# Adafruit_0_54_Alphanumeric_STEMMA_QT.net
KiCad netlist of a schematic drawn in EAGLE
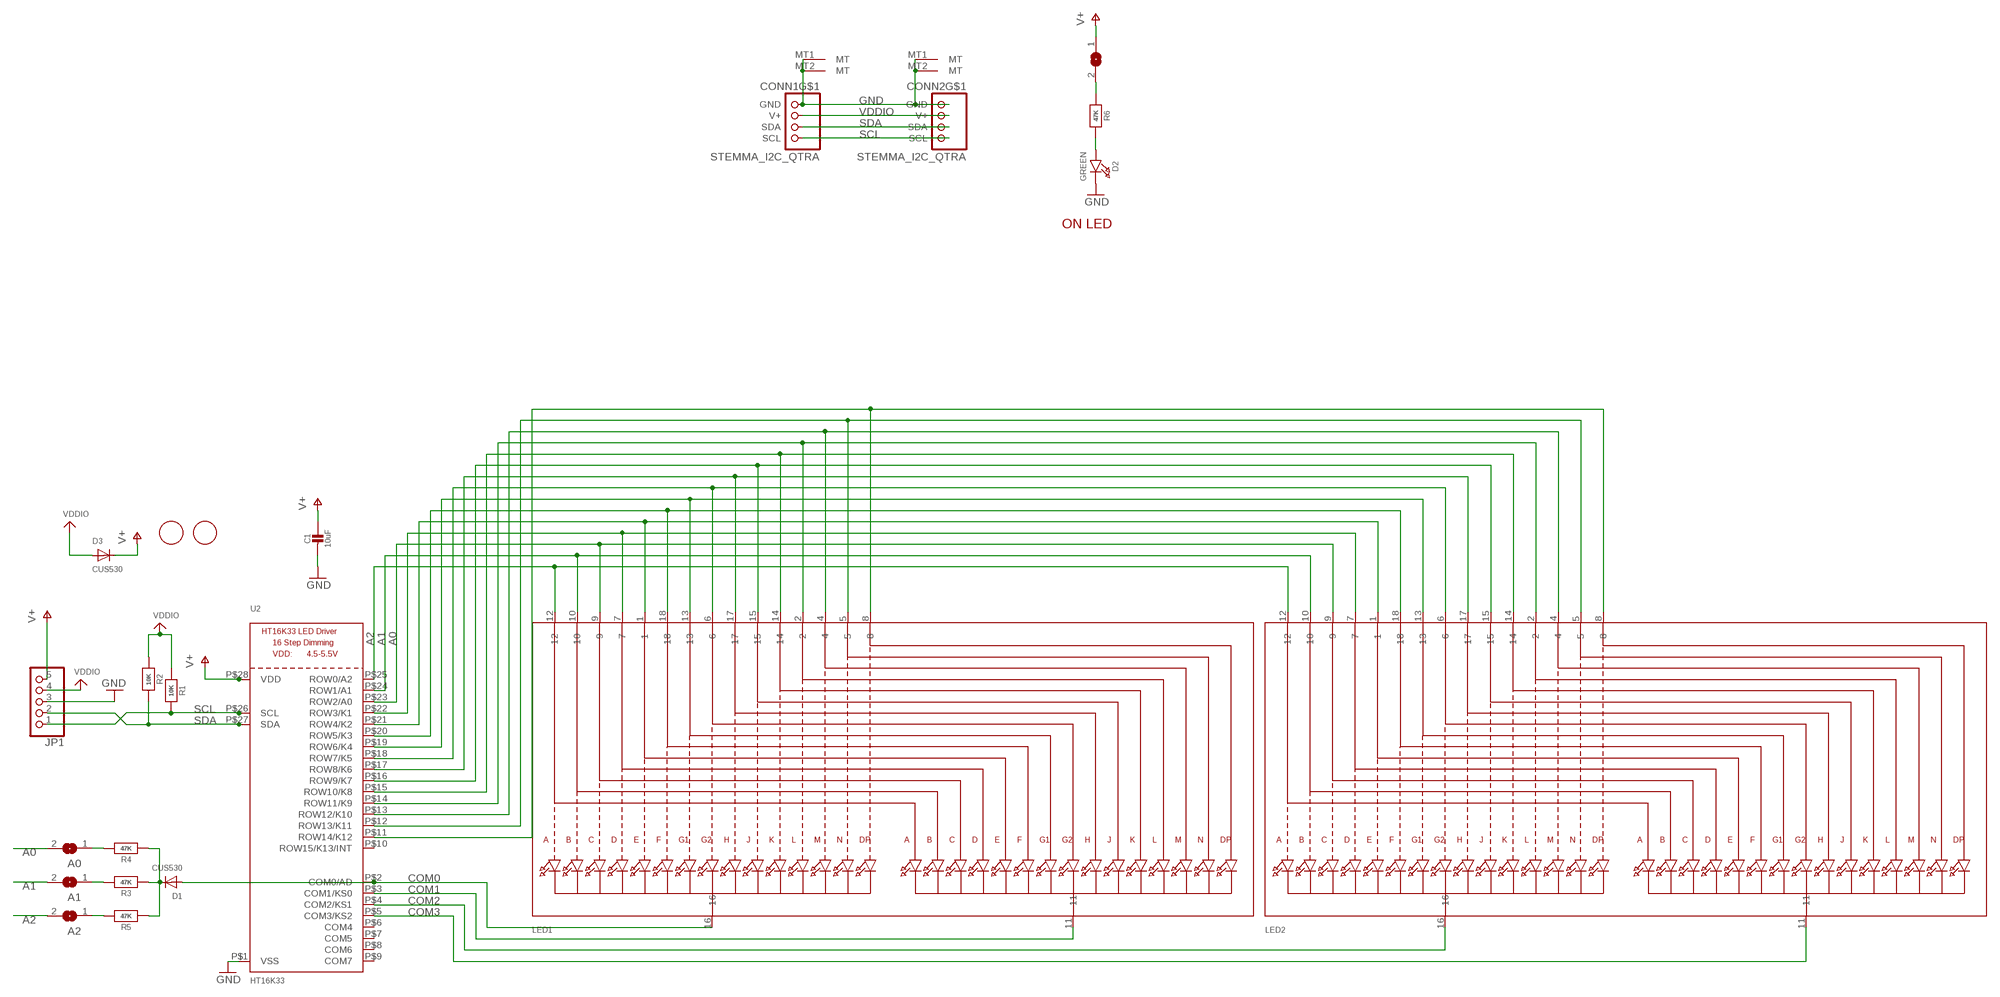
[diagram p0: schematic, sheet 1]

(export (version "E")
  (design (tool "Eeschema 10.0.6"))
  (components
    (comp (ref "A0")
      (value "SOLDERJUMPERREFLOW_NOPASTE")
      (footprint "eagle-import:SOLDERJUMPER_REFLOW_NOPASTE")
      (libsource (lib "eagle-import") (part "SOLDERJUMPERREFLOW_NOPASTE"))
    )
    (comp (ref "A1")
      (value "SOLDERJUMPERREFLOW_NOPASTE")
      (footprint "eagle-import:SOLDERJUMPER_REFLOW_NOPASTE")
      (libsource (lib "eagle-import") (part "SOLDERJUMPERREFLOW_NOPASTE"))
    )
    (comp (ref "A2")
      (value "SOLDERJUMPERREFLOW_NOPASTE")
      (footprint "eagle-import:SOLDERJUMPER_REFLOW_NOPASTE")
      (libsource (lib "eagle-import") (part "SOLDERJUMPERREFLOW_NOPASTE"))
    )
    (comp (ref "C1")
      (value "10uF")
      (footprint "eagle-import:0805-NO")
      (libsource (lib "eagle-import") (part "CAP_CERAMIC0805-NOOUTLINE"))
    )
    (comp (ref "CONN1")
      (value "STEMMA_I2C_QTRA")
      (footprint "eagle-import:JST_SH4_RA")
      (libsource (lib "eagle-import") (part "STEMMA_I2C_QTRA"))
    )
    (comp (ref "CONN2")
      (value "STEMMA_I2C_QTRA")
      (footprint "eagle-import:JST_SH4_RA")
      (libsource (lib "eagle-import") (part "STEMMA_I2C_QTRA"))
    )
    (comp (ref "D1")
      (value "CUS530")
      (footprint "eagle-import:SOD-323F")
      (libsource (lib "eagle-import") (part "DIODESOD-323F"))
    )
    (comp (ref "D2")
      (value "GREEN")
      (footprint "eagle-import:CHIPLED_0603_NOOUTLINE")
      (libsource (lib "eagle-import") (part "LED0603_NOOUTLINE"))
    )
    (comp (ref "D3")
      (value "CUS530")
      (footprint "eagle-import:SOD-323F")
      (libsource (lib "eagle-import") (part "DIODESOD-323F"))
    )
    (comp (ref "JP1")
      (value "HEADER-1X570MIL")
      (footprint "eagle-import:1X05_ROUND_70")
      (libsource (lib "eagle-import") (part "HEADER-1X570MIL"))
    )
    (comp (ref "LED1")
      (value "DISP_SEGMENT_STARBURST_DUAL_COMMONCATHODE")
      (footprint "eagle-import:SEGMENT_STARTBUST_DUAL_KWA-541CBB")
      (libsource (lib "eagle-import") (part "DISP_SEGMENT_STARBURST_DUAL_COMMONCATHODE"))
    )
    (comp (ref "LED2")
      (value "DISP_SEGMENT_STARBURST_DUAL_COMMONCATHODE")
      (footprint "eagle-import:SEGMENT_STARTBUST_DUAL_KWA-541CBB")
      (libsource (lib "eagle-import") (part "DISP_SEGMENT_STARBURST_DUAL_COMMONCATHODE"))
    )
    (comp (ref "LEDJMP")
      (value "SOLDERJUMPERCLOSED")
      (footprint "eagle-import:SOLDERJUMPER_CLOSEDWIRE")
      (libsource (lib "eagle-import") (part "SOLDERJUMPERCLOSED"))
    )
    (comp (ref "R1")
      (value "10K")
      (footprint "eagle-import:0603-NO")
      (libsource (lib "eagle-import") (part "RESISTOR_0603_NOOUT"))
    )
    (comp (ref "R2")
      (value "10K")
      (footprint "eagle-import:0603-NO")
      (libsource (lib "eagle-import") (part "RESISTOR_0603_NOOUT"))
    )
    (comp (ref "R3")
      (value "47K")
      (footprint "eagle-import:0603-NO")
      (libsource (lib "eagle-import") (part "RESISTOR_0603_NOOUT"))
    )
    (comp (ref "R4")
      (value "47K")
      (footprint "eagle-import:0603-NO")
      (libsource (lib "eagle-import") (part "RESISTOR_0603_NOOUT"))
    )
    (comp (ref "R5")
      (value "47K")
      (footprint "eagle-import:0603-NO")
      (libsource (lib "eagle-import") (part "RESISTOR_0603_NOOUT"))
    )
    (comp (ref "R6")
      (value "47K")
      (footprint "eagle-import:0603-NO")
      (libsource (lib "eagle-import") (part "RESISTOR_0603_NOOUT"))
    )
    (comp (ref "U$1")
      (value "FIDUCIAL")
      (footprint "eagle-import:FIDUCIAL_1MM")
      (libsource (lib "eagle-import") (part "FIDUCIAL"))
    )
    (comp (ref "U$2")
      (value "FIDUCIAL")
      (footprint "eagle-import:FIDUCIAL_1MM")
      (libsource (lib "eagle-import") (part "FIDUCIAL"))
    )
    (comp (ref "U2")
      (value "HT16K33")
      (footprint "eagle-import:SOP28_300MIL_SKINNY")
      (libsource (lib "eagle-import") (part "HT16K33_SOP28_SKINNY"))
    )
  )
  (nets
    (net (code "1") (name "/A0") (class "Default")
      (node (ref "A0") (pin "2") (pinfunction "2_2") (pintype "passive"))
      (node (ref "LED1") (pin "9") (pinfunction "9_9") (pintype "bidirectional"))
      (node (ref "LED2") (pin "9") (pinfunction "9_9") (pintype "bidirectional"))
      (node (ref "U2") (pin "P$23") (pinfunction "ROW2/A0_P$23") (pintype "bidirectional"))
    )
    (net (code "2") (name "/A1") (class "Default")
      (node (ref "A1") (pin "2") (pinfunction "2_2") (pintype "passive"))
      (node (ref "LED1") (pin "10") (pinfunction "10_10") (pintype "bidirectional"))
      (node (ref "LED2") (pin "10") (pinfunction "10_10") (pintype "bidirectional"))
      (node (ref "U2") (pin "P$24") (pinfunction "ROW1/A1_P$24") (pintype "bidirectional"))
    )
    (net (code "3") (name "/A2") (class "Default")
      (node (ref "A2") (pin "2") (pinfunction "2_2") (pintype "passive"))
      (node (ref "LED1") (pin "12") (pinfunction "12_12") (pintype "bidirectional"))
      (node (ref "LED2") (pin "12") (pinfunction "12_12") (pintype "bidirectional"))
      (node (ref "U2") (pin "P$25") (pinfunction "ROW0/A2_P$25") (pintype "bidirectional"))
    )
    (net (code "4") (name "/COM0") (class "Default")
      (node (ref "D1") (pin "A") (pinfunction "A_A") (pintype "passive"))
      (node (ref "LED1") (pin "16") (pinfunction "16_16") (pintype "bidirectional"))
      (node (ref "U2") (pin "P$2") (pinfunction "COM0/AD_P$2") (pintype "bidirectional"))
    )
    (net (code "5") (name "/COM1") (class "Default")
      (node (ref "LED1") (pin "11") (pinfunction "11_11") (pintype "bidirectional"))
      (node (ref "U2") (pin "P$3") (pinfunction "COM1/KS0_P$3") (pintype "bidirectional"))
    )
    (net (code "6") (name "/COM2") (class "Default")
      (node (ref "LED2") (pin "16") (pinfunction "16_16") (pintype "bidirectional"))
      (node (ref "U2") (pin "P$4") (pinfunction "COM2/KS1_P$4") (pintype "bidirectional"))
    )
    (net (code "7") (name "/COM3") (class "Default")
      (node (ref "LED2") (pin "11") (pinfunction "11_11") (pintype "bidirectional"))
      (node (ref "U2") (pin "P$5") (pinfunction "COM3/KS2_P$5") (pintype "bidirectional"))
    )
    (net (code "8") (name "/SCL") (class "Default")
      (node (ref "CONN1") (pin "4") (pinfunction "SCL_4") (pintype "passive"))
      (node (ref "CONN2") (pin "4") (pinfunction "SCL_4") (pintype "passive"))
      (node (ref "JP1") (pin "1") (pinfunction "1_1") (pintype "passive"))
      (node (ref "R1") (pin "2") (pinfunction "2_2") (pintype "passive"))
      (node (ref "U2") (pin "P$26") (pinfunction "SCL_P$26") (pintype "bidirectional"))
    )
    (net (code "9") (name "/SDA") (class "Default")
      (node (ref "CONN1") (pin "3") (pinfunction "SDA_3") (pintype "passive"))
      (node (ref "CONN2") (pin "3") (pinfunction "SDA_3") (pintype "passive"))
      (node (ref "JP1") (pin "2") (pinfunction "2_2") (pintype "passive"))
      (node (ref "R2") (pin "2") (pinfunction "2_2") (pintype "passive"))
      (node (ref "U2") (pin "P$27") (pinfunction "SDA_P$27") (pintype "bidirectional"))
    )
    (net (code "10") (name "GND") (class "Default")
      (node (ref "C1") (pin "2") (pinfunction "2_2") (pintype "passive"))
      (node (ref "CONN1") (pin "1") (pinfunction "GND_1") (pintype "passive"))
      (node (ref "CONN1") (pin "MT1") (pinfunction "MT_MT1") (pintype "bidirectional"))
      (node (ref "CONN1") (pin "MT2") (pinfunction "MT_MT2") (pintype "bidirectional"))
      (node (ref "CONN2") (pin "1") (pinfunction "GND_1") (pintype "passive"))
      (node (ref "CONN2") (pin "MT1") (pinfunction "MT_MT1") (pintype "bidirectional"))
      (node (ref "CONN2") (pin "MT2") (pinfunction "MT_MT2") (pintype "bidirectional"))
      (node (ref "D2") (pin "C") (pinfunction "C_C") (pintype "passive"))
      (node (ref "JP1") (pin "3") (pinfunction "3_3") (pintype "passive"))
      (node (ref "U2") (pin "P$1") (pinfunction "VSS_P$1") (pintype "bidirectional"))
    )
    (net (code "11") (name "Net-(A0-Pad1)") (class "Default")
      (node (ref "A0") (pin "1") (pinfunction "1_1") (pintype "passive"))
      (node (ref "R4") (pin "2") (pinfunction "2_2") (pintype "passive"))
    )
    (net (code "12") (name "Net-(A1-Pad1)") (class "Default")
      (node (ref "A1") (pin "1") (pinfunction "1_1") (pintype "passive"))
      (node (ref "R3") (pin "2") (pinfunction "2_2") (pintype "passive"))
    )
    (net (code "13") (name "Net-(A2-Pad1)") (class "Default")
      (node (ref "A2") (pin "1") (pinfunction "1_1") (pintype "passive"))
      (node (ref "R5") (pin "2") (pinfunction "2_2") (pintype "passive"))
    )
    (net (code "14") (name "Net-(D1-PadC)") (class "Default")
      (node (ref "D1") (pin "C") (pinfunction "C_C") (pintype "passive"))
      (node (ref "R3") (pin "1") (pinfunction "1_1") (pintype "passive"))
      (node (ref "R4") (pin "1") (pinfunction "1_1") (pintype "passive"))
      (node (ref "R5") (pin "1") (pinfunction "1_1") (pintype "passive"))
    )
    (net (code "15") (name "Net-(D2-PadA)") (class "Default")
      (node (ref "D2") (pin "A") (pinfunction "A_A") (pintype "passive"))
      (node (ref "R6") (pin "2") (pinfunction "2_2") (pintype "passive"))
    )
    (net (code "16") (name "Net-(LEDJMP-Pad2)") (class "Default")
      (node (ref "LEDJMP") (pin "2") (pinfunction "2_2") (pintype "passive"))
      (node (ref "R6") (pin "1") (pinfunction "1_1") (pintype "passive"))
    )
    (net (code "17") (name "Net-(U2-ROW3{slash}K1)") (class "Default")
      (node (ref "LED1") (pin "7") (pinfunction "7_7") (pintype "bidirectional"))
      (node (ref "LED2") (pin "7") (pinfunction "7_7") (pintype "bidirectional"))
      (node (ref "U2") (pin "P$22") (pinfunction "ROW3/K1_P$22") (pintype "bidirectional"))
    )
    (net (code "18") (name "Net-(U2-ROW4{slash}K2)") (class "Default")
      (node (ref "LED1") (pin "1") (pinfunction "1_1") (pintype "bidirectional"))
      (node (ref "LED2") (pin "1") (pinfunction "1_1") (pintype "bidirectional"))
      (node (ref "U2") (pin "P$21") (pinfunction "ROW4/K2_P$21") (pintype "bidirectional"))
    )
    (net (code "19") (name "Net-(U2-ROW5{slash}K3)") (class "Default")
      (node (ref "LED1") (pin "18") (pinfunction "18_18") (pintype "bidirectional"))
      (node (ref "LED2") (pin "18") (pinfunction "18_18") (pintype "bidirectional"))
      (node (ref "U2") (pin "P$20") (pinfunction "ROW5/K3_P$20") (pintype "bidirectional"))
    )
    (net (code "20") (name "Net-(U2-ROW6{slash}K4)") (class "Default")
      (node (ref "LED1") (pin "13") (pinfunction "13_13") (pintype "bidirectional"))
      (node (ref "LED2") (pin "13") (pinfunction "13_13") (pintype "bidirectional"))
      (node (ref "U2") (pin "P$19") (pinfunction "ROW6/K4_P$19") (pintype "bidirectional"))
    )
    (net (code "21") (name "Net-(U2-ROW7{slash}K5)") (class "Default")
      (node (ref "LED1") (pin "6") (pinfunction "6_6") (pintype "bidirectional"))
      (node (ref "LED2") (pin "6") (pinfunction "6_6") (pintype "bidirectional"))
      (node (ref "U2") (pin "P$18") (pinfunction "ROW7/K5_P$18") (pintype "bidirectional"))
    )
    (net (code "22") (name "Net-(U2-ROW8{slash}K6)") (class "Default")
      (node (ref "LED1") (pin "17") (pinfunction "17_17") (pintype "bidirectional"))
      (node (ref "LED2") (pin "17") (pinfunction "17_17") (pintype "bidirectional"))
      (node (ref "U2") (pin "P$17") (pinfunction "ROW8/K6_P$17") (pintype "bidirectional"))
    )
    (net (code "23") (name "Net-(U2-ROW9{slash}K7)") (class "Default")
      (node (ref "LED1") (pin "15") (pinfunction "15_15") (pintype "bidirectional"))
      (node (ref "LED2") (pin "15") (pinfunction "15_15") (pintype "bidirectional"))
      (node (ref "U2") (pin "P$16") (pinfunction "ROW9/K7_P$16") (pintype "bidirectional"))
    )
    (net (code "24") (name "Net-(U2-ROW10{slash}K8)") (class "Default")
      (node (ref "LED1") (pin "14") (pinfunction "14_14") (pintype "bidirectional"))
      (node (ref "LED2") (pin "14") (pinfunction "14_14") (pintype "bidirectional"))
      (node (ref "U2") (pin "P$15") (pinfunction "ROW10/K8_P$15") (pintype "bidirectional"))
    )
    (net (code "25") (name "Net-(U2-ROW11{slash}K9)") (class "Default")
      (node (ref "LED1") (pin "2") (pinfunction "2_2") (pintype "bidirectional"))
      (node (ref "LED2") (pin "2") (pinfunction "2_2") (pintype "bidirectional"))
      (node (ref "U2") (pin "P$14") (pinfunction "ROW11/K9_P$14") (pintype "bidirectional"))
    )
    (net (code "26") (name "Net-(U2-ROW12{slash}K10)") (class "Default")
      (node (ref "LED1") (pin "4") (pinfunction "4_4") (pintype "bidirectional"))
      (node (ref "LED2") (pin "4") (pinfunction "4_4") (pintype "bidirectional"))
      (node (ref "U2") (pin "P$13") (pinfunction "ROW12/K10_P$13") (pintype "bidirectional"))
    )
    (net (code "27") (name "Net-(U2-ROW13{slash}K11)") (class "Default")
      (node (ref "LED1") (pin "5") (pinfunction "5_5") (pintype "bidirectional"))
      (node (ref "LED2") (pin "5") (pinfunction "5_5") (pintype "bidirectional"))
      (node (ref "U2") (pin "P$12") (pinfunction "ROW13/K11_P$12") (pintype "bidirectional"))
    )
    (net (code "28") (name "Net-(U2-ROW14{slash}K12)") (class "Default")
      (node (ref "LED1") (pin "8") (pinfunction "8_8") (pintype "bidirectional"))
      (node (ref "LED2") (pin "8") (pinfunction "8_8") (pintype "bidirectional"))
      (node (ref "U2") (pin "P$11") (pinfunction "ROW14/K12_P$11") (pintype "bidirectional"))
    )
    (net (code "29") (name "V+") (class "Default")
      (node (ref "C1") (pin "1") (pinfunction "1_1") (pintype "passive"))
      (node (ref "D3") (pin "C") (pinfunction "C_C") (pintype "passive"))
      (node (ref "JP1") (pin "5") (pinfunction "5_5") (pintype "passive"))
      (node (ref "LEDJMP") (pin "1") (pinfunction "1_1") (pintype "passive"))
      (node (ref "U2") (pin "P$28") (pinfunction "VDD_P$28") (pintype "bidirectional"))
    )
    (net (code "30") (name "VDDIO") (class "Default")
      (node (ref "CONN1") (pin "2") (pinfunction "V+_2") (pintype "passive"))
      (node (ref "CONN2") (pin "2") (pinfunction "V+_2") (pintype "passive"))
      (node (ref "D3") (pin "A") (pinfunction "A_A") (pintype "passive"))
      (node (ref "JP1") (pin "4") (pinfunction "4_4") (pintype "passive"))
      (node (ref "R1") (pin "1") (pinfunction "1_1") (pintype "passive"))
      (node (ref "R2") (pin "1") (pinfunction "1_1") (pintype "passive"))
    )
    (net (code "31") (name "unconnected-(U2-COM4-PadP$6)") (class "Default")
      (node (ref "U2") (pin "P$6") (pinfunction "COM4_P$6") (pintype "bidirectional"))
    )
    (net (code "32") (name "unconnected-(U2-COM5-PadP$7)") (class "Default")
      (node (ref "U2") (pin "P$7") (pinfunction "COM5_P$7") (pintype "bidirectional"))
    )
    (net (code "33") (name "unconnected-(U2-COM6-PadP$8)") (class "Default")
      (node (ref "U2") (pin "P$8") (pinfunction "COM6_P$8") (pintype "bidirectional"))
    )
    (net (code "34") (name "unconnected-(U2-COM7-PadP$9)") (class "Default")
      (node (ref "U2") (pin "P$9") (pinfunction "COM7_P$9") (pintype "bidirectional"))
    )
    (net (code "35") (name "unconnected-(U2-ROW15{slash}K13{slash}INT-PadP$10)") (class "Default")
      (node (ref "U2") (pin "P$10") (pinfunction "ROW15/K13/INT_P$10") (pintype "bidirectional"))
    )
  )
)
